# 05_MCU.net
KiCad netlist of a schematic drawn in Altium Designer
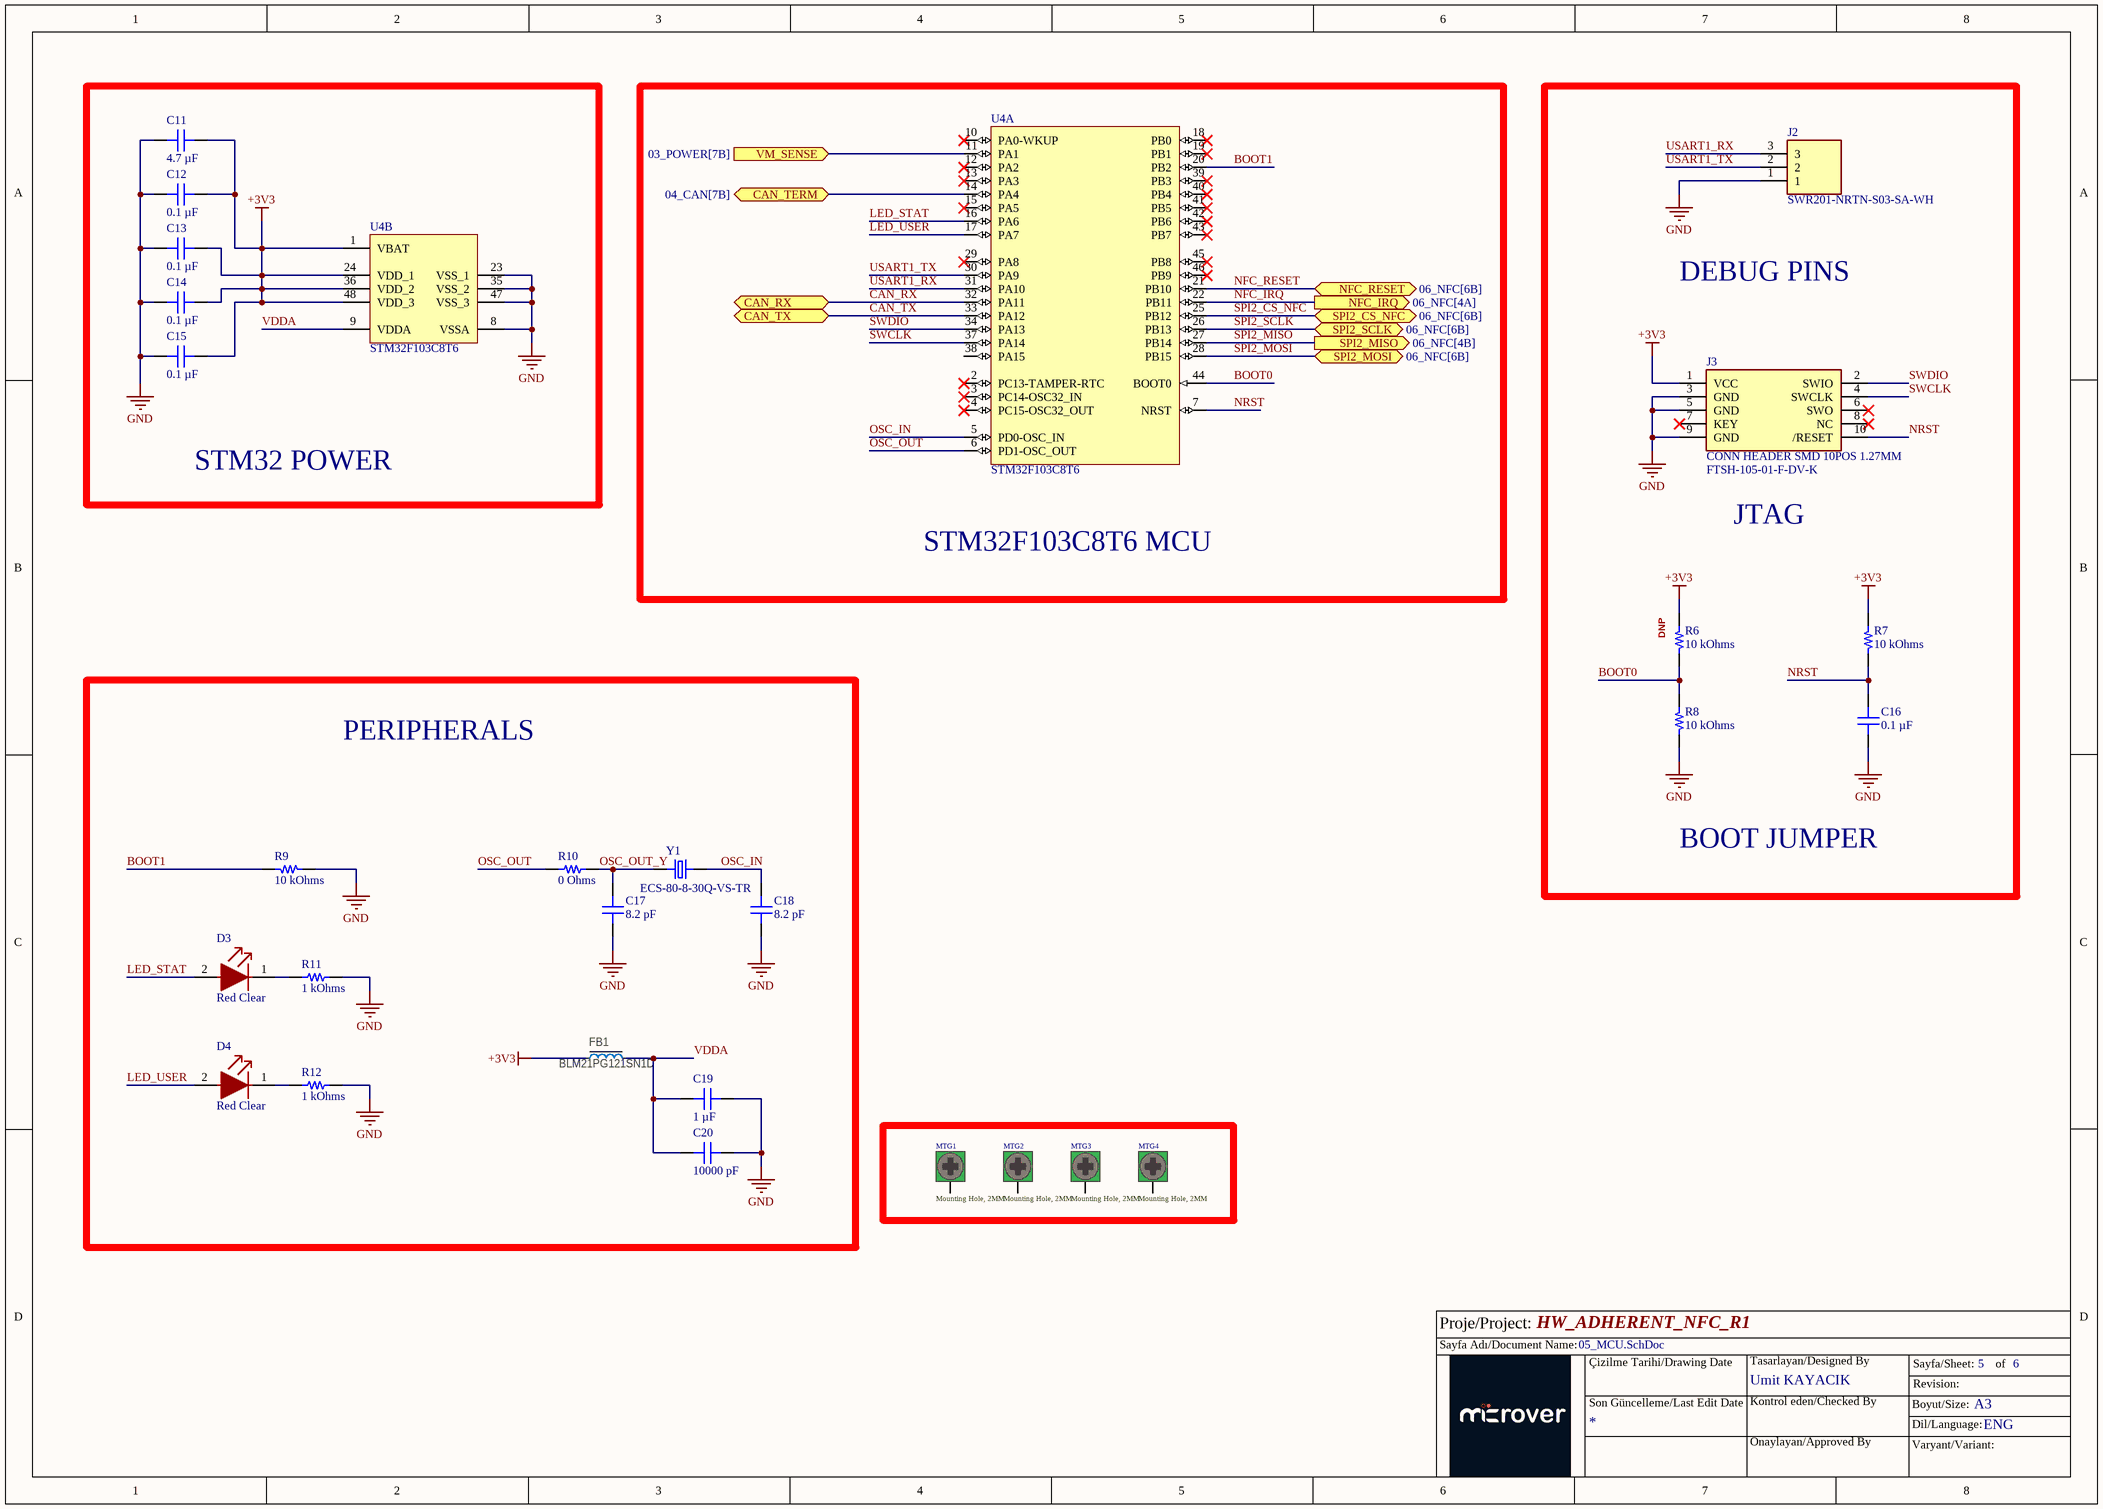
[diagram p0: 05_MCU.SchDoc]

(export (version "E")
  (design (tool "Eeschema 10.0.6"))
  (components
    (comp (ref "C11")
      (value "4.7 µF")
      (footprint "CAP 0805_2012")
      (description "CAP CER 4.7UF 50V X7R 0805")
      (fields
        (field (name "PART NUMBER") "GRM21BZ71H475KE15K")
        (field (name "CAPACITANCE") "4.7 µF")
        (field (name "MANUFACTURER") "Murata Electronics")
      )
      (libsource (lib "Celestial Altium Library - altium_library") (part "Capacitor"))
    )
    (comp (ref "C12")
      (value "GCM188R71H104KA57J")
      (footprint "CAP 0603_1608")
      (description "CAP CER 0.1UF 50V X7R 0603")
      (fields
        (field (name "CAPACITANCE") "0.1 µF")
        (field (name "MANUFACTURER") "Murata Electronics")
        (field (name "TOLERANCE") "±10%")
      )
      (libsource (lib "Celestial Altium Library - altium_library") (part "Capacitor"))
    )
    (comp (ref "C13")
      (value "GCM188R71H104KA57J")
      (footprint "CAP 0603_1608")
      (description "CAP CER 0.1UF 50V X7R 0603")
      (fields
        (field (name "CAPACITANCE") "0.1 µF")
        (field (name "MANUFACTURER") "Murata Electronics")
        (field (name "TOLERANCE") "±10%")
      )
      (libsource (lib "Celestial Altium Library - altium_library") (part "Capacitor"))
    )
    (comp (ref "C14")
      (value "GCM188R71H104KA57J")
      (footprint "CAP 0603_1608")
      (description "CAP CER 0.1UF 50V X7R 0603")
      (fields
        (field (name "CAPACITANCE") "0.1 µF")
        (field (name "MANUFACTURER") "Murata Electronics")
        (field (name "TOLERANCE") "±10%")
      )
      (libsource (lib "Celestial Altium Library - altium_library") (part "Capacitor"))
    )
    (comp (ref "C15")
      (value "GCM188R71H104KA57J")
      (footprint "CAP 0603_1608")
      (description "CAP CER 0.1UF 50V X7R 0603")
      (fields
        (field (name "CAPACITANCE") "0.1 µF")
        (field (name "MANUFACTURER") "Murata Electronics")
        (field (name "TOLERANCE") "±10%")
      )
      (libsource (lib "Celestial Altium Library - altium_library") (part "Capacitor"))
    )
    (comp (ref "C16")
      (value "GCM188R71H104KA57J")
      (footprint "CAP 0603_1608")
      (description "CAP CER 0.1UF 50V X7R 0603")
      (fields
        (field (name "CAPACITANCE") "0.1 µF")
        (field (name "MANUFACTURER") "Murata Electronics")
        (field (name "TOLERANCE") "±10%")
      )
      (libsource (lib "Celestial Altium Library - altium_library") (part "Capacitor"))
    )
    (comp (ref "C17")
      (value "8.2 pF")
      (footprint "CAP 0402_1005")
      (description "CAP0402 COG 8.2PF 5% 25V")
      (fields
        (field (name "PART NUMBER") "GMC04CG8R2J25NT")
        (field (name "CAPACITANCE") "8.2 pF")
        (field (name "MANUFACTURER") "Cal-Chip Electronics, Inc.")
      )
      (libsource (lib "Celestial Altium Library - altium_library") (part "Capacitor"))
    )
    (comp (ref "C18")
      (value "8.2 pF")
      (footprint "CAP 0402_1005")
      (description "CAP0402 COG 8.2PF 5% 25V")
      (fields
        (field (name "PART NUMBER") "GMC04CG8R2J25NT")
        (field (name "CAPACITANCE") "8.2 pF")
        (field (name "MANUFACTURER") "Cal-Chip Electronics, Inc.")
      )
      (libsource (lib "Celestial Altium Library - altium_library") (part "Capacitor"))
    )
    (comp (ref "C19")
      (value "1 µF")
      (footprint "CAP 0603_1608")
      (description "CAP0603 X7R 1UF 10% 25V")
      (fields
        (field (name "PART NUMBER") "GMC10X7R105K25NT")
        (field (name "CAPACITANCE") "1 µF")
        (field (name "MANUFACTURER") "Cal-Chip Electronics, Inc.")
      )
      (libsource (lib "Celestial Altium Library - altium_library") (part "Capacitor"))
    )
    (comp (ref "C20")
      (value "10000 pF")
      (footprint "CAP 0603_1608")
      (description "CAP CER 0603 10NF 16V X7R 10%")
      (fields
        (field (name "PART NUMBER") "C0603C103K4RECTU")
        (field (name "CAPACITANCE") "10000 pF")
        (field (name "MANUFACTURER") "KEMET")
      )
      (libsource (lib "Celestial Altium Library - altium_library") (part "Capacitor"))
    )
    (comp (ref "D3")
      (value "LED RED CLEAR SMD")
      (footprint "Lite-On_RED_0603")
      (description "Red 631nm LED Indication - Discrete 2V 0603 (1608 Metric)")
      (fields
        (field (name "MANUFACTURER") "Lite-On Inc.")
        (field (name "MANUFACTURER PART NUMBER") "LTST-C191KRKT")
        (field (name "COLOR") "Red Clear")
      )
      (libsource (lib "HW_ADHERENT_NFC_R1_L3") (part "LTST-C191KRKT_2"))
    )
    (comp (ref "D4")
      (value "LED RED CLEAR SMD")
      (footprint "Lite-On_RED_0603")
      (description "Red 631nm LED Indication - Discrete 2V 0603 (1608 Metric)")
      (fields
        (field (name "MANUFACTURER") "Lite-On Inc.")
        (field (name "MANUFACTURER PART NUMBER") "LTST-C191KRKT")
        (field (name "COLOR") "Red Clear")
      )
      (libsource (lib "HW_ADHERENT_NFC_R1_L3") (part "LTST-C191KRKT_2"))
    )
    (comp (ref "FB1")
      (value "BLM21PG121SN1D")
      (footprint "INDC2012X11L")
      (description "Ferrite Bead, 120 Ohm @ 100MHz, 500mA, 250 mOhm Max")
      (fields
        (field (name "PART NUMBER") "FB0402-120R@100M-500mA")
        (field (name "MANUFACTURER") "Murata")
        (field (name "AUTHOR") "rsk")
      )
      (libsource (lib "HW_PEINFO_CRANECTRL_KEY20_R1") (part "FB0402-120R@100M-500mA"))
    )
    (comp (ref "J2")
      (value "SWR201-NRTN-S03-SA-WH")
      (footprint "SHDR3W50P0X200_1X3_790X460X630P")
      (description "Connector")
      (libsource (lib "HW_PEINFO_CRANECTRL_KEY20_R1") (part "SWR201-NRTN-S03-SA-WH"))
    )
    (comp (ref "J3")
      (value "CONN HEADER SMD 10POS 1.27MM")
      (footprint "Samtec_0_MFG")
      (description "Connector Header Surface Mount 10 position 0.050\" (1.27mm)")
      (fields (field (name "MANUFACTURER PART NUMBER") "FTSH-105-01-F-DV-K"))
      (libsource (lib "HW_PEINFO_RF_RECEIVER_R1") (part "FTSH-105-01-F-DV-K"))
    )
    (comp (ref "MTG1")
      (value "Mounting Hole, 2MM")
      (footprint "MTG-PTH-2MM")
      (libsource (lib "HW_PEINFO_CRANECTRL_KEY20_R1") (part "MTG2MM"))
    )
    (comp (ref "MTG2")
      (value "Mounting Hole, 2MM")
      (footprint "MTG-PTH-2MM")
      (libsource (lib "HW_PEINFO_CRANECTRL_KEY20_R1") (part "MTG2MM"))
    )
    (comp (ref "MTG3")
      (value "Mounting Hole, 2MM")
      (footprint "MTG-PTH-2MM")
      (libsource (lib "HW_PEINFO_CRANECTRL_KEY20_R1") (part "MTG2MM"))
    )
    (comp (ref "MTG4")
      (value "Mounting Hole, 2MM")
      (footprint "MTG-PTH-2MM")
      (libsource (lib "HW_PEINFO_CRANECTRL_KEY20_R1") (part "MTG2MM"))
    )
    (comp (ref "R6")
      (value "10 kOhms")
      (footprint "RES 0402_1005")
      (description "RES 10K OHM 1% 1/16W 0402")
      (fields
        (field (name "PART NUMBER") "RMCF0402FT10K0")
        (field (name "MANUFACTURER") "Stackpole Electronics Inc")
      )
      (libsource (lib "Celestial Altium Library - altium_library") (part "Resistor"))
    )
    (comp (ref "R7")
      (value "10 kOhms")
      (footprint "RES 0402_1005")
      (description "RES 10K OHM 1% 1/16W 0402")
      (fields
        (field (name "PART NUMBER") "RMCF0402FT10K0")
        (field (name "MANUFACTURER") "Stackpole Electronics Inc")
      )
      (libsource (lib "Celestial Altium Library - altium_library") (part "Resistor"))
    )
    (comp (ref "R8")
      (value "10 kOhms")
      (footprint "RES 0402_1005")
      (description "RES 10K OHM 1% 1/16W 0402")
      (fields
        (field (name "PART NUMBER") "RMCF0402FT10K0")
        (field (name "MANUFACTURER") "Stackpole Electronics Inc")
      )
      (libsource (lib "Celestial Altium Library - altium_library") (part "Resistor"))
    )
    (comp (ref "R9")
      (value "10 kOhms")
      (footprint "RES 0402_1005")
      (description "RES 10K OHM 1% 1/16W 0402")
      (fields
        (field (name "PART NUMBER") "RMCF0402FT10K0")
        (field (name "MANUFACTURER") "Stackpole Electronics Inc")
      )
      (libsource (lib "Celestial Altium Library - altium_library") (part "Resistor"))
    )
    (comp (ref "R10")
      (value "0 Ohms")
      (footprint "RES 0402_1005")
      (description "RES 0 OHM JUMPER 1/16W 0402")
      (fields
        (field (name "PART NUMBER") "RMCF0402ZT0R00")
        (field (name "MANUFACTURER") "Stackpole Electronics Inc")
      )
      (libsource (lib "Celestial Altium Library - altium_library") (part "Resistor"))
    )
    (comp (ref "R11")
      (value "1 kOhms")
      (footprint "RES 0402_1005")
      (description "RES 1K OHM 1% 1/16W 0402")
      (fields
        (field (name "PART NUMBER") "RMCF0402FT1K00")
        (field (name "MANUFACTURER") "Stackpole Electronics Inc")
      )
      (libsource (lib "Celestial Altium Library - altium_library") (part "Resistor"))
    )
    (comp (ref "R12")
      (value "1 kOhms")
      (footprint "RES 0402_1005")
      (description "RES 1K OHM 1% 1/16W 0402")
      (fields
        (field (name "PART NUMBER") "RMCF0402FT1K00")
        (field (name "MANUFACTURER") "Stackpole Electronics Inc")
      )
      (libsource (lib "Celestial Altium Library - altium_library") (part "Resistor"))
    )
    (comp (ref "U4")
      (value "STM32F103C8T6")
      (footprint "LQFP48_STM")
      (fields (field (name "LCSC PART NUMBER") "C8734"))
      (libsource (lib "HW_PEINFO_RF_RECEIVER_R1") (part "STM32F103C8T6"))
    )
    (comp (ref "Y1")
      (value "ECS-80-8-30Q-VS-TR")
      (footprint "XTAL_ECS-80-8-30Q-VS-TR")
      (description "8 MHz Â±30ppm Crystal 8pF 100 Ohms 2-SMD, No Lead")
      (fields (field (name "MF") "ECS Inc."))
      (libsource (lib "HW_PEINFO_CRANECTRL_KEY20_R1") (part "ECS-80-8-30Q-VS-TR"))
    )
  )
  (nets
    (net (code "1") (name "+3V3") (class "Default")
      (node (ref "C11") (pin "2") (pinfunction "2_2") (pintype "passive"))
      (node (ref "C12") (pin "1") (pinfunction "1_1") (pintype "passive"))
      (node (ref "C13") (pin "1") (pinfunction "1_1") (pintype "passive"))
      (node (ref "C14") (pin "1") (pinfunction "1_1") (pintype "passive"))
      (node (ref "C15") (pin "1") (pinfunction "1_1") (pintype "passive"))
      (node (ref "FB1") (pin "1") (pinfunction "1_1") (pintype "passive"))
      (node (ref "J3") (pin "1") (pinfunction "VCC_1") (pintype "passive"))
      (node (ref "R6") (pin "1") (pinfunction "1_1") (pintype "passive"))
      (node (ref "R7") (pin "1") (pinfunction "1_1") (pintype "passive"))
      (node (ref "U4") (pin "1") (pinfunction "VBAT_1") (pintype "power_in"))
      (node (ref "U4") (pin "24") (pinfunction "VDD_1_24") (pintype "power_in"))
      (node (ref "U4") (pin "36") (pinfunction "VDD_2_36") (pintype "power_in"))
      (node (ref "U4") (pin "48") (pinfunction "VDD_3_48") (pintype "power_in"))
    )
    (net (code "2") (name "/BOOT0") (class "Default")
      (node (ref "R6") (pin "2") (pinfunction "2_2") (pintype "passive"))
      (node (ref "R8") (pin "1") (pinfunction "1_1") (pintype "passive"))
      (node (ref "U4") (pin "44") (pinfunction "BOOT0_44") (pintype "input"))
    )
    (net (code "3") (name "/BOOT1") (class "Default")
      (node (ref "R9") (pin "2") (pinfunction "2_2") (pintype "passive"))
      (node (ref "U4") (pin "20") (pinfunction "PB2_20") (pintype "bidirectional"))
    )
    (net (code "4") (name "/CAN_RX") (class "Default")
      (node (ref "U4") (pin "32") (pinfunction "PA11_32") (pintype "bidirectional"))
    )
    (net (code "5") (name "/CAN_TERM") (class "Default")
      (node (ref "U4") (pin "14") (pinfunction "PA4_14") (pintype "bidirectional"))
    )
    (net (code "6") (name "/CAN_TX") (class "Default")
      (node (ref "U4") (pin "33") (pinfunction "PA12_33") (pintype "bidirectional"))
    )
    (net (code "7") (name "/LED_STAT") (class "Default")
      (node (ref "D3") (pin "2") (pinfunction "A_2") (pintype "passive"))
      (node (ref "U4") (pin "16") (pinfunction "PA6_16") (pintype "bidirectional"))
    )
    (net (code "8") (name "/LED_USER") (class "Default")
      (node (ref "D4") (pin "2") (pinfunction "A_2") (pintype "passive"))
      (node (ref "U4") (pin "17") (pinfunction "PA7_17") (pintype "bidirectional"))
    )
    (net (code "9") (name "/NFC_IRQ") (class "Default")
      (node (ref "U4") (pin "22") (pinfunction "PB11_22") (pintype "bidirectional"))
    )
    (net (code "10") (name "/NFC_RESET") (class "Default")
      (node (ref "U4") (pin "21") (pinfunction "PB10_21") (pintype "bidirectional"))
    )
    (net (code "11") (name "/NRST") (class "Default")
      (node (ref "C16") (pin "1") (pinfunction "1_1") (pintype "passive"))
      (node (ref "J3") (pin "10") (pinfunction "/RESET_10") (pintype "passive"))
      (node (ref "R7") (pin "2") (pinfunction "2_2") (pintype "passive"))
      (node (ref "U4") (pin "7") (pinfunction "NRST_7") (pintype "bidirectional"))
    )
    (net (code "12") (name "/OSC_IN") (class "Default")
      (node (ref "C18") (pin "2") (pinfunction "2_2") (pintype "passive"))
      (node (ref "U4") (pin "5") (pinfunction "PD0-OSC_IN_5") (pintype "bidirectional"))
      (node (ref "Y1") (pin "2") (pinfunction "OUT/IN_2") (pintype "passive"))
    )
    (net (code "13") (name "/OSC_OUT") (class "Default")
      (node (ref "R10") (pin "1") (pinfunction "1_1") (pintype "passive"))
      (node (ref "U4") (pin "6") (pinfunction "PD1-OSC_OUT_6") (pintype "bidirectional"))
    )
    (net (code "14") (name "/OSC_OUT_Y") (class "Default")
      (node (ref "C17") (pin "2") (pinfunction "2_2") (pintype "passive"))
      (node (ref "R10") (pin "2") (pinfunction "2_2") (pintype "passive"))
      (node (ref "Y1") (pin "1") (pinfunction "IN/OUT_1") (pintype "passive"))
    )
    (net (code "15") (name "/SPI2_CS_NFC") (class "Default")
      (node (ref "U4") (pin "25") (pinfunction "PB12_25") (pintype "bidirectional"))
    )
    (net (code "16") (name "/SPI2_MISO") (class "Default")
      (node (ref "U4") (pin "27") (pinfunction "PB14_27") (pintype "bidirectional"))
    )
    (net (code "17") (name "/SPI2_MOSI") (class "Default")
      (node (ref "U4") (pin "28") (pinfunction "PB15_28") (pintype "bidirectional"))
    )
    (net (code "18") (name "/SPI2_SCLK") (class "Default")
      (node (ref "U4") (pin "26") (pinfunction "PB13_26") (pintype "bidirectional"))
    )
    (net (code "19") (name "/SWCLK") (class "Default")
      (node (ref "J3") (pin "4") (pinfunction "SWCLK_4") (pintype "passive"))
      (node (ref "U4") (pin "37") (pinfunction "PA14_37") (pintype "bidirectional"))
    )
    (net (code "20") (name "/SWDIO") (class "Default")
      (node (ref "J3") (pin "2") (pinfunction "SWIO_2") (pintype "passive"))
      (node (ref "U4") (pin "34") (pinfunction "PA13_34") (pintype "bidirectional"))
    )
    (net (code "21") (name "/USART1_RX") (class "Default")
      (node (ref "J2") (pin "3") (pinfunction "3_3") (pintype "passive"))
      (node (ref "U4") (pin "31") (pinfunction "PA10_31") (pintype "bidirectional"))
    )
    (net (code "22") (name "/USART1_TX") (class "Default")
      (node (ref "J2") (pin "2") (pinfunction "2_2") (pintype "passive"))
      (node (ref "U4") (pin "30") (pinfunction "PA9_30") (pintype "bidirectional"))
    )
    (net (code "23") (name "/VDDA") (class "Default")
      (node (ref "C19") (pin "1") (pinfunction "1_1") (pintype "passive"))
      (node (ref "C20") (pin "1") (pinfunction "1_1") (pintype "passive"))
      (node (ref "FB1") (pin "2") (pinfunction "2_2") (pintype "passive"))
      (node (ref "U4") (pin "9") (pinfunction "VDDA_9") (pintype "power_in"))
    )
    (net (code "24") (name "/VM_SENSE") (class "Default")
      (node (ref "U4") (pin "11") (pinfunction "PA1_11") (pintype "bidirectional"))
    )
    (net (code "25") (name "GND") (class "Default")
      (node (ref "C11") (pin "1") (pinfunction "1_1") (pintype "passive"))
      (node (ref "C12") (pin "2") (pinfunction "2_2") (pintype "passive"))
      (node (ref "C13") (pin "2") (pinfunction "2_2") (pintype "passive"))
      (node (ref "C14") (pin "2") (pinfunction "2_2") (pintype "passive"))
      (node (ref "C15") (pin "2") (pinfunction "2_2") (pintype "passive"))
      (node (ref "C16") (pin "2") (pinfunction "2_2") (pintype "passive"))
      (node (ref "C17") (pin "1") (pinfunction "1_1") (pintype "passive"))
      (node (ref "C18") (pin "1") (pinfunction "1_1") (pintype "passive"))
      (node (ref "C19") (pin "2") (pinfunction "2_2") (pintype "passive"))
      (node (ref "C20") (pin "2") (pinfunction "2_2") (pintype "passive"))
      (node (ref "J2") (pin "1") (pinfunction "1_1") (pintype "passive"))
      (node (ref "J3") (pin "3") (pinfunction "GND_3") (pintype "passive"))
      (node (ref "J3") (pin "5") (pinfunction "GND_5") (pintype "passive"))
      (node (ref "J3") (pin "9") (pinfunction "GND_9") (pintype "passive"))
      (node (ref "R11") (pin "2") (pinfunction "2_2") (pintype "passive"))
      (node (ref "R12") (pin "2") (pinfunction "2_2") (pintype "passive"))
      (node (ref "R8") (pin "2") (pinfunction "2_2") (pintype "passive"))
      (node (ref "R9") (pin "1") (pinfunction "1_1") (pintype "passive"))
      (node (ref "U4") (pin "23") (pinfunction "VSS_1_23") (pintype "passive"))
      (node (ref "U4") (pin "35") (pinfunction "VSS_2_35") (pintype "passive"))
      (node (ref "U4") (pin "47") (pinfunction "VSS_3_47") (pintype "passive"))
      (node (ref "U4") (pin "8") (pinfunction "VSSA_8") (pintype "passive"))
    )
    (net (code "26") (name "Net-(D3-C)") (class "Default")
      (node (ref "D3") (pin "1") (pinfunction "C_1") (pintype "passive"))
      (node (ref "R11") (pin "1") (pinfunction "1_1") (pintype "passive"))
    )
    (net (code "27") (name "Net-(D4-C)") (class "Default")
      (node (ref "D4") (pin "1") (pinfunction "C_1") (pintype "passive"))
      (node (ref "R12") (pin "1") (pinfunction "1_1") (pintype "passive"))
    )
    (net (code "28") (name "unconnected-(J3-KEY-Pad7)") (class "Default")
      (node (ref "J3") (pin "7") (pinfunction "KEY_7") (pintype "passive+no_connect"))
    )
    (net (code "29") (name "unconnected-(J3-NC-Pad8)") (class "Default")
      (node (ref "J3") (pin "8") (pinfunction "NC_8") (pintype "passive+no_connect"))
    )
    (net (code "30") (name "unconnected-(J3-SWO-Pad6)") (class "Default")
      (node (ref "J3") (pin "6") (pinfunction "SWO_6") (pintype "passive+no_connect"))
    )
    (net (code "31") (name "unconnected-(MTG1-Pad0)") (class "Default")
      (node (ref "MTG1") (pin "0") (pinfunction "0_0") (pintype "passive"))
    )
    (net (code "32") (name "unconnected-(MTG2-Pad0)") (class "Default")
      (node (ref "MTG2") (pin "0") (pinfunction "0_0") (pintype "passive"))
    )
    (net (code "33") (name "unconnected-(MTG3-Pad0)") (class "Default")
      (node (ref "MTG3") (pin "0") (pinfunction "0_0") (pintype "passive"))
    )
    (net (code "34") (name "unconnected-(MTG4-Pad0)") (class "Default")
      (node (ref "MTG4") (pin "0") (pinfunction "0_0") (pintype "passive"))
    )
    (net (code "35") (name "unconnected-(U4A-PA0-WKUP-Pad10)") (class "Default")
      (node (ref "U4") (pin "10") (pinfunction "PA0-WKUP_10") (pintype "bidirectional+no_connect"))
    )
    (net (code "36") (name "unconnected-(U4A-PA2-Pad12)") (class "Default")
      (node (ref "U4") (pin "12") (pinfunction "PA2_12") (pintype "bidirectional+no_connect"))
    )
    (net (code "37") (name "unconnected-(U4A-PA3-Pad13)") (class "Default")
      (node (ref "U4") (pin "13") (pinfunction "PA3_13") (pintype "bidirectional+no_connect"))
    )
    (net (code "38") (name "unconnected-(U4A-PA5-Pad15)") (class "Default")
      (node (ref "U4") (pin "15") (pinfunction "PA5_15") (pintype "bidirectional+no_connect"))
    )
    (net (code "39") (name "unconnected-(U4A-PA8-Pad29)") (class "Default")
      (node (ref "U4") (pin "29") (pinfunction "PA8_29") (pintype "bidirectional+no_connect"))
    )
    (net (code "40") (name "unconnected-(U4A-PA15-Pad38)") (class "Default")
      (node (ref "U4") (pin "38") (pinfunction "PA15_38") (pintype "bidirectional"))
    )
    (net (code "41") (name "unconnected-(U4A-PB0-Pad18)") (class "Default")
      (node (ref "U4") (pin "18") (pinfunction "PB0_18") (pintype "bidirectional+no_connect"))
    )
    (net (code "42") (name "unconnected-(U4A-PB1-Pad19)") (class "Default")
      (node (ref "U4") (pin "19") (pinfunction "PB1_19") (pintype "bidirectional+no_connect"))
    )
    (net (code "43") (name "unconnected-(U4A-PB3-Pad39)") (class "Default")
      (node (ref "U4") (pin "39") (pinfunction "PB3_39") (pintype "bidirectional+no_connect"))
    )
    (net (code "44") (name "unconnected-(U4A-PB4-Pad40)") (class "Default")
      (node (ref "U4") (pin "40") (pinfunction "PB4_40") (pintype "bidirectional+no_connect"))
    )
    (net (code "45") (name "unconnected-(U4A-PB5-Pad41)") (class "Default")
      (node (ref "U4") (pin "41") (pinfunction "PB5_41") (pintype "bidirectional+no_connect"))
    )
    (net (code "46") (name "unconnected-(U4A-PB6-Pad42)") (class "Default")
      (node (ref "U4") (pin "42") (pinfunction "PB6_42") (pintype "bidirectional+no_connect"))
    )
    (net (code "47") (name "unconnected-(U4A-PB7-Pad43)") (class "Default")
      (node (ref "U4") (pin "43") (pinfunction "PB7_43") (pintype "bidirectional+no_connect"))
    )
    (net (code "48") (name "unconnected-(U4A-PB8-Pad45)") (class "Default")
      (node (ref "U4") (pin "45") (pinfunction "PB8_45") (pintype "bidirectional+no_connect"))
    )
    (net (code "49") (name "unconnected-(U4A-PB9-Pad46)") (class "Default")
      (node (ref "U4") (pin "46") (pinfunction "PB9_46") (pintype "bidirectional+no_connect"))
    )
    (net (code "50") (name "unconnected-(U4A-PC13-TAMPER-RTC-Pad2)") (class "Default")
      (node (ref "U4") (pin "2") (pinfunction "PC13-TAMPER-RTC_2") (pintype "bidirectional+no_connect"))
    )
    (net (code "51") (name "unconnected-(U4A-PC14-OSC32_IN-Pad3)") (class "Default")
      (node (ref "U4") (pin "3") (pinfunction "PC14-OSC32_IN_3") (pintype "bidirectional+no_connect"))
    )
    (net (code "52") (name "unconnected-(U4A-PC15-OSC32_OUT-Pad4)") (class "Default")
      (node (ref "U4") (pin "4") (pinfunction "PC15-OSC32_OUT_4") (pintype "bidirectional+no_connect"))
    )
  )
)
